# SSBtag_afe.net
KiCad netlist of a schematic drawn in Altium Designer
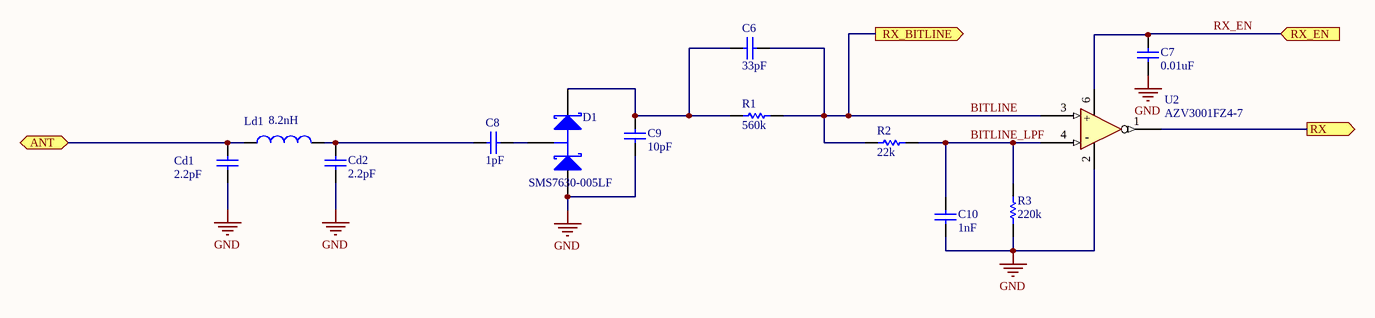
[diagram p0: SSBtag_afe.SchDoc]

(export (version "E")
  (design (tool "Eeschema 10.0.6"))
  (components
    (comp (ref "C6")
      (value "33pF")
      (footprint "0402")
      (description "Ceramic Capacitor (Surface Mount)")
      (fields
        (field (name "MANUFACTURER") "Generic Ceramic Chip Cap (TBD)")
        (field (name "Comment") "GCQ1555C1H330JB01D")
      )
      (libsource (lib "wisp") (part "Cap"))
    )
    (comp (ref "C7")
      (value "0.01uF")
      (footprint "0402")
      (description "Ceramic Capacitor (Surface Mount)")
      (fields
        (field (name "MANUFACTURER") "Generic Ceramic Chip Cap (TBD)")
        (field (name "Comment") "GCM155R71H103KA55D")
      )
      (libsource (lib "wisp") (part "Cap"))
    )
    (comp (ref "C8")
      (value "1pF")
      (footprint "0402")
      (description "Ceramic Capacitor (Surface Mount)")
      (fields
        (field (name "MANUFACTURER") "Generic Ceramic Chip Cap (TBD)")
        (field (name "Comment") "GCQ1555C1H1R0WB01D")
      )
      (libsource (lib "wisp") (part "Cap"))
    )
    (comp (ref "C9")
      (value "10pF")
      (footprint "0402")
      (description "Ceramic Capacitor (Surface Mount)")
      (fields
        (field (name "MANUFACTURER") "Generic Ceramic Chip Cap (TBD)")
        (field (name "Comment") "GCQ1555C1H100FB01D")
      )
      (libsource (lib "wisp") (part "Cap"))
    )
    (comp (ref "C10")
      (value "1nF")
      (footprint "0402")
      (description "Ceramic Capacitor (Surface Mount)")
      (fields
        (field (name "MANUFACTURER") "Generic Ceramic Chip Cap (TBD)")
        (field (name "Comment") "GCM1555C1H102JA16J")
      )
      (libsource (lib "wisp") (part "Cap"))
    )
    (comp (ref "Cd1")
      (value "2.2pF")
      (footprint "0402")
      (description "Ceramic Capacitor (Surface Mount)")
      (fields
        (field (name "MANUFACTURER") "Generic Ceramic Chip Cap (TBD)")
        (field (name "Comment") "GJM1555C1H1R0WB01D")
      )
      (libsource (lib "wisp") (part "Cap"))
    )
    (comp (ref "Cd2")
      (value "2.2pF")
      (footprint "0402")
      (description "Ceramic Capacitor (Surface Mount)")
      (fields
        (field (name "MANUFACTURER") "Generic Ceramic Chip Cap (TBD)")
        (field (name "Comment") "GJM1555C1H1R0WB01D")
      )
      (libsource (lib "wisp") (part "Cap"))
    )
    (comp (ref "D1")
      (value "SMS7630-005LF")
      (footprint "SOT23")
      (description "Schottky Diode, Two in Series, Small Package SOT-23")
      (fields (field (name "MANUFACTURER") "Skyworks"))
      (libsource (lib "bfp") (part "SMS7630-005LF"))
    )
    (comp (ref "Ld1")
      (value "8.2nH")
      (footprint "0402")
      (description "Inductor (Surface Mount)")
      (fields (field (name "Comment") "LQW15AN6N6G8ZD"))
      (libsource (lib "*") (part "Ind"))
    )
    (comp (ref "R1")
      (value "560k")
      (footprint "0402")
      (description "Chip Resistor (Surface Mount)")
      (fields
        (field (name "MANUFACTURER") "Generic Chip Res (TBD)")
        (field (name "Comment") "CRCW0402560KFKED")
      )
      (libsource (lib "wisp") (part "Res"))
    )
    (comp (ref "R2")
      (value "22k")
      (footprint "0402")
      (description "Chip Resistor (Surface Mount)")
      (fields
        (field (name "MANUFACTURER") "Generic Chip Res (TBD)")
        (field (name "Comment") "CRCW040222K0FKEDC")
      )
      (libsource (lib "wisp") (part "Res"))
    )
    (comp (ref "R3")
      (value "220k")
      (footprint "0402")
      (description "Chip Resistor (Surface Mount)")
      (fields
        (field (name "MANUFACTURER") "Generic Chip Res (TBD)")
        (field (name "Comment") "CRCW0402220KFKED")
      )
      (libsource (lib "wisp") (part "Res"))
    )
    (comp (ref "U2")
      (value "AZV3001FZ4-7")
      (footprint "X2DFN1410-6")
      (libsource (lib "bfp") (part "AZV3001FZ4-7"))
    )
  )
  (nets
    (net (code "1") (name "/ANT") (class "Default")
      (node (ref "Cd1") (pin "2") (pinfunction "2_2") (pintype "passive"))
      (node (ref "Ld1") (pin "1") (pinfunction "1_1") (pintype "passive"))
    )
    (net (code "2") (name "/BITLINE") (class "Default")
      (node (ref "C6") (pin "2") (pinfunction "2_2") (pintype "passive"))
      (node (ref "R1") (pin "2") (pinfunction "2_2") (pintype "passive"))
      (node (ref "R2") (pin "1") (pinfunction "1_1") (pintype "passive"))
      (node (ref "U2") (pin "3") (pinfunction "IN+_3") (pintype "input"))
    )
    (net (code "3") (name "/BITLINE_LPF") (class "Default")
      (node (ref "C10") (pin "2") (pinfunction "2_2") (pintype "passive"))
      (node (ref "R2") (pin "2") (pinfunction "2_2") (pintype "passive"))
      (node (ref "R3") (pin "2") (pinfunction "2_2") (pintype "passive"))
      (node (ref "U2") (pin "4") (pinfunction "In-_4") (pintype "input"))
    )
    (net (code "4") (name "/RX") (class "Default")
      (node (ref "U2") (pin "1") (pinfunction "OUT_1") (pintype "output"))
    )
    (net (code "5") (name "/RX_EN") (class "Default")
      (node (ref "C7") (pin "2") (pinfunction "2_2") (pintype "passive"))
      (node (ref "U2") (pin "6") (pinfunction "VDD_6") (pintype "power_in"))
    )
    (net (code "6") (name "GND") (class "Default")
      (node (ref "C10") (pin "1") (pinfunction "1_1") (pintype "passive"))
      (node (ref "C7") (pin "1") (pinfunction "1_1") (pintype "passive"))
      (node (ref "C9") (pin "1") (pinfunction "1_1") (pintype "passive"))
      (node (ref "Cd1") (pin "1") (pinfunction "1_1") (pintype "passive"))
      (node (ref "Cd2") (pin "1") (pinfunction "1_1") (pintype "passive"))
      (node (ref "D1") (pin "1") (pinfunction "A_1") (pintype "passive"))
      (node (ref "R3") (pin "1") (pinfunction "1_1") (pintype "passive"))
      (node (ref "U2") (pin "2") (pinfunction "Gnd_2") (pintype "power_in"))
    )
    (net (code "7") (name "Net-(C8-Pad1)") (class "Default")
      (node (ref "C8") (pin "1") (pinfunction "1_1") (pintype "passive"))
      (node (ref "Cd2") (pin "2") (pinfunction "2_2") (pintype "passive"))
      (node (ref "Ld1") (pin "2") (pinfunction "2_2") (pintype "passive"))
    )
    (net (code "8") (name "Net-(D1-C)") (class "Default")
      (node (ref "C8") (pin "2") (pinfunction "2_2") (pintype "passive"))
      (node (ref "D1") (pin "3") (pinfunction "C_3") (pintype "passive"))
    )
    (net (code "9") (name "Net-(D1-K)") (class "Default")
      (node (ref "C6") (pin "1") (pinfunction "1_1") (pintype "passive"))
      (node (ref "C9") (pin "2") (pinfunction "2_2") (pintype "passive"))
      (node (ref "D1") (pin "2") (pinfunction "K_2") (pintype "passive"))
      (node (ref "R1") (pin "1") (pinfunction "1_1") (pintype "passive"))
    )
  )
)
